# perifericos.net
KiCad netlist of a schematic drawn in Altium Designer
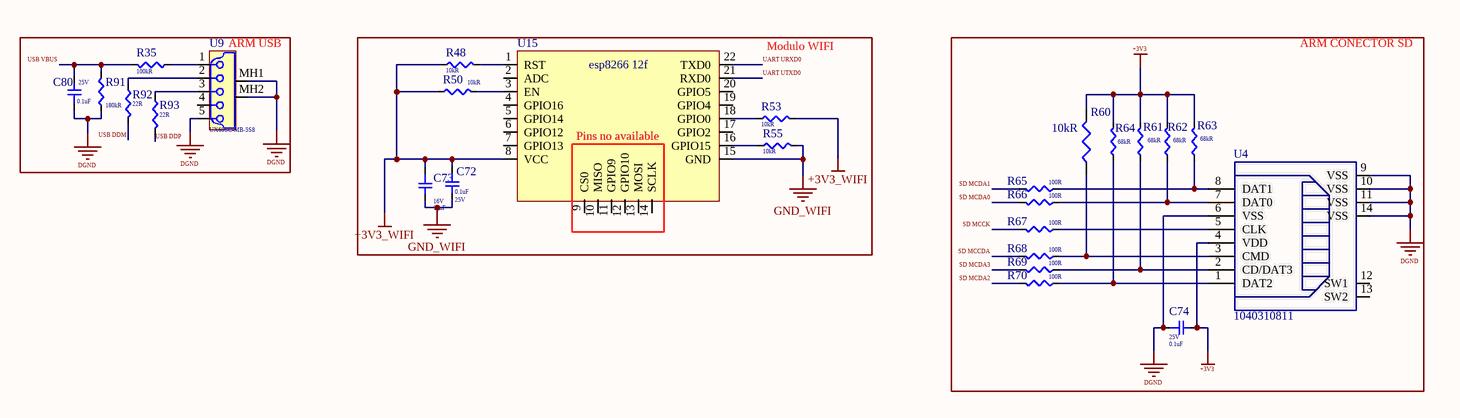
[diagram p0: perifericos.SchDoc]

(export (version "E")
  (design (tool "Eeschema 10.0.6"))
  (components
    (comp (ref "C72")
      (value "CAP_CC0805KRX7R8BB104_YAGEO")
      (footprint "CAP smd 0805 ok")
      (description "CAPACITOR, 0805, 100NF, 25V, REEL 4000")
      (fields
        (field (name "TOLERANCE") "10%")
        (field (name "VOLTAGE RATING") "25V")
        (field (name "CAPACITANCE") "0.1uF")
      )
      (libsource (lib "Cap") (part "CAP_CC0805KRX7R8BB104_YAGEO"))
    )
    (comp (ref "C73")
      (value "CAP_CL21A106KOCL3RC")
      (footprint "CAP smd 0805 OK")
      (description "CAP CER 10UF 16V X5R 0805")
      (fields
        (field (name "TOLERANCE") "10%")
        (field (name "VOLTAGE RATING") "16V")
        (field (name "CAPACITANCE") "10uF")
      )
      (libsource (lib "Cap") (part "CAP_CL21A106KOCL3RC"))
    )
    (comp (ref "C74")
      (value "CAP_CC0805KRX7R8BB104_YAGEO")
      (footprint "CAP smd 0805 ok")
      (description "CAPACITOR, 0805, 100NF, 25V, REEL 4000")
      (fields
        (field (name "TOLERANCE") "10%")
        (field (name "VOLTAGE RATING") "25V")
        (field (name "CAPACITANCE") "0.1uF")
      )
      (libsource (lib "Cap") (part "CAP_CC0805KRX7R8BB104_YAGEO"))
    )
    (comp (ref "C80")
      (value "CAP_CC0805KRX7R8BB104_YAGEO")
      (footprint "CAP smd 0805 ok")
      (description "CAPACITOR, 0805, 100NF, 25V, REEL 4000")
      (fields
        (field (name "TOLERANCE") "10%")
        (field (name "VOLTAGE RATING") "25V")
        (field (name "CAPACITANCE") "0.1uF")
      )
      (libsource (lib "Cap") (part "CAP_CC0805KRX7R8BB104_YAGEO"))
    )
    (comp (ref "R35")
      (value "AC0805JR-07100KL")
      (footprint "res 0805 ok")
      (description "Thick Film Resistors - SMD 0805  100K ohm 5% 1/8W")
      (fields (field (name "TOLERANCE") "5%") (field (name "RESISTANCE") "100kR"))
      (libsource (lib "res") (part "AC0805JR-07100KL"))
    )
    (comp (ref "R48")
      (value "RC0805JR-0710KL")
      (footprint "res 0805 ok")
      (description "Res Thick Film smd 0805 10K Ohm 5% 1/8W")
      (fields (field (name "TOLERANCE") "5%") (field (name "RESISTANCE") "10kR"))
      (libsource (lib "res") (part "RC0805JR-0710KL"))
    )
    (comp (ref "R50")
      (value "RC0805JR-0710KL")
      (footprint "res 0805 ok")
      (description "Res Thick Film smd 0805 10K Ohm 5% 1/8W")
      (fields (field (name "TOLERANCE") "5%") (field (name "RESISTANCE") "10kR"))
      (libsource (lib "res") (part "RC0805JR-0710KL"))
    )
    (comp (ref "R53")
      (value "RC0805JR-0710KL")
      (footprint "res 0805 ok")
      (description "Res Thick Film smd 0805 10K Ohm 5% 1/8W")
      (fields (field (name "TOLERANCE") "5%") (field (name "RESISTANCE") "10kR"))
      (libsource (lib "res") (part "RC0805JR-0710KL"))
    )
    (comp (ref "R55")
      (value "RC0805JR-0710KL")
      (footprint "res 0805 ok")
      (description "Res Thick Film smd 0805 10K Ohm 5% 1/8W")
      (fields (field (name "TOLERANCE") "5%") (field (name "RESISTANCE") "10kR"))
      (libsource (lib "res") (part "RC0805JR-0710KL"))
    )
    (comp (ref "R60")
      (value "RC1206JR-0768KL")
      (footprint "Res 1206 ok")
      (description "Res Thick Film smd 1206 10K Ohm 1% 0.25W(1/4W)")
      (fields (field (name "TOLERANCE") "1%") (field (name "RESISTANCE") "10kR"))
      (libsource (lib "res") (part "RC1206FR-0710KL"))
    )
    (comp (ref "R61")
      (value "RC1206JR-0768KL")
      (footprint "Res 1206 ok")
      (description "Thick Film Resistors smd 1206(3216) 68K OHM 5% 250mW")
      (fields (field (name "TOLERANCE") "5%") (field (name "RESISTANCE") "68kR"))
      (libsource (lib "res") (part "RC1206JR-0768KL"))
    )
    (comp (ref "R62")
      (value "RC1206JR-0768KL")
      (footprint "Res 1206 ok")
      (description "Thick Film Resistors smd 1206(3216) 68K OHM 5% 250mW")
      (fields (field (name "TOLERANCE") "5%") (field (name "RESISTANCE") "68kR"))
      (libsource (lib "res") (part "RC1206JR-0768KL"))
    )
    (comp (ref "R63")
      (value "RC1206JR-0768KL")
      (footprint "Res 1206 ok")
      (description "Thick Film Resistors smd 1206(3216) 68K OHM 5% 250mW")
      (fields (field (name "TOLERANCE") "5%") (field (name "RESISTANCE") "68kR"))
      (libsource (lib "res") (part "RC1206JR-0768KL"))
    )
    (comp (ref "R64")
      (value "RC1206JR-0768KL")
      (footprint "Res 1206 ok")
      (description "Thick Film Resistors smd 1206(3216) 68K OHM 5% 250mW")
      (fields (field (name "TOLERANCE") "5%") (field (name "RESISTANCE") "68kR"))
      (libsource (lib "res") (part "RC1206JR-0768KL"))
    )
    (comp (ref "R65")
      (value "RC1206JR-07100RL")
      (footprint "Res 1206 ok")
      (description "Thick Film Resistors SMD 1206 (3264)  100 OHM 5% 250mW")
      (fields (field (name "TOLERANCE") "5%") (field (name "RESISTANCE") "100R"))
      (libsource (lib "res") (part "RC1206JR-07100RL"))
    )
    (comp (ref "R66")
      (value "RC1206JR-07100RL")
      (footprint "Res 1206 ok")
      (description "Thick Film Resistors SMD 1206 (3264)  100 OHM 5% 250mW")
      (fields (field (name "TOLERANCE") "5%") (field (name "RESISTANCE") "100R"))
      (libsource (lib "res") (part "RC1206JR-07100RL"))
    )
    (comp (ref "R67")
      (value "RC1206JR-07100RL")
      (footprint "Res 1206 ok")
      (description "Thick Film Resistors SMD 1206 (3264)  100 OHM 5% 250mW")
      (fields (field (name "TOLERANCE") "5%") (field (name "RESISTANCE") "100R"))
      (libsource (lib "res") (part "RC1206JR-07100RL"))
    )
    (comp (ref "R68")
      (value "RC1206JR-07100RL")
      (footprint "Res 1206 ok")
      (description "Thick Film Resistors SMD 1206 (3264)  100 OHM 5% 250mW")
      (fields (field (name "TOLERANCE") "5%") (field (name "RESISTANCE") "100R"))
      (libsource (lib "res") (part "RC1206JR-07100RL"))
    )
    (comp (ref "R69")
      (value "RC1206JR-07100RL")
      (footprint "Res 1206 ok")
      (description "Thick Film Resistors SMD 1206 (3264)  100 OHM 5% 250mW")
      (fields (field (name "TOLERANCE") "5%") (field (name "RESISTANCE") "100R"))
      (libsource (lib "res") (part "RC1206JR-07100RL"))
    )
    (comp (ref "R70")
      (value "RC1206JR-07100RL")
      (footprint "Res 1206 ok")
      (description "Thick Film Resistors SMD 1206 (3264)  100 OHM 5% 250mW")
      (fields (field (name "TOLERANCE") "5%") (field (name "RESISTANCE") "100R"))
      (libsource (lib "res") (part "RC1206JR-07100RL"))
    )
    (comp (ref "R91")
      (value "RC1206JR-07180KL")
      (footprint "Res 1206 ok")
      (description "RES SMD 1206 180K OHM 5% 1/4W")
      (fields (field (name "TOLERANCE") "5%") (field (name "RESISTANCE") "180kR"))
      (libsource (lib "res") (part "RC1206JR-07180KL"))
    )
    (comp (ref "R92")
      (value "RC0805JR-0722RL")
      (footprint "res 0805 ok")
      (description "Res Thick Film smd  0805 22 Ohm 5% 1/8W")
      (fields (field (name "TOLERANCE") "5%") (field (name "RESISTANCE") "22R"))
      (libsource (lib "res") (part "RC0805JR-0722RL"))
    )
    (comp (ref "R93")
      (value "RC0805JR-0722RL")
      (footprint "res 0805 ok")
      (description "Res Thick Film smd  0805 22 Ohm 5% 1/8W")
      (fields (field (name "TOLERANCE") "5%") (field (name "RESISTANCE") "22R"))
      (libsource (lib "res") (part "RC0805JR-0722RL"))
    )
    (comp (ref "U4")
      (value "1040310811")
      (footprint "micro sd")
      (libsource (lib "others") (part "1040310811"))
    )
    (comp (ref "U9")
      (value "UX60SC-MB-5S8")
      (description "Conn Mini USB 2.0 Type B RCP 5 POS 0.8mm Solder RA SMD 5 Terminal 1 Port Embossed T/R")
      (libsource (lib "conectors") (part "UX60SC-MB-5S8"))
    )
    (comp (ref "U15")
      (value "esp8266 12f")
      (footprint "modulo wifi ok")
      (libsource (lib "ic") (part "esp8266 12f"))
    )
  )
  (nets
    (net (code "1") (name "+3V3") (class "Default")
      (node (ref "C74") (pin "22") (pinfunction "22_22") (pintype "passive"))
      (node (ref "R60") (pin "1") (pinfunction "1_1") (pintype "passive"))
      (node (ref "R61") (pin "1") (pintype "passive"))
      (node (ref "R62") (pin "1") (pintype "passive"))
      (node (ref "R63") (pin "1") (pintype "passive"))
      (node (ref "R64") (pin "1") (pintype "passive"))
      (node (ref "U4") (pin "4") (pinfunction "VDD_4") (pintype "passive"))
    )
    (net (code "2") (name "+3V3_WIFI") (class "Default")
      (node (ref "C72") (pin "23") (pinfunction "23_23") (pintype "passive"))
      (node (ref "C73") (pin "23") (pinfunction "23_23") (pintype "passive"))
      (node (ref "R48") (pin "2") (pinfunction "2_2") (pintype "passive"))
      (node (ref "R50") (pin "2") (pinfunction "2_2") (pintype "passive"))
      (node (ref "R53") (pin "1") (pintype "passive"))
      (node (ref "U15") (pin "8") (pinfunction "VCC_8") (pintype "passive"))
    )
    (net (code "3") (name "/SD MCCDA") (class "Default") (node (ref "R68") (pin "1") (pintype "passive")))
    (net (code "4") (name "/SD MCCK") (class "Default") (node (ref "R67") (pin "1") (pintype "passive")))
    (net (code "5") (name "/SD MCDA0") (class "Default") (node (ref "R66") (pin "1") (pintype "passive")))
    (net (code "6") (name "/SD MCDA1") (class "Default") (node (ref "R65") (pin "1") (pintype "passive")))
    (net (code "7") (name "/SD MCDA2") (class "Default") (node (ref "R70") (pin "1") (pintype "passive")))
    (net (code "8") (name "/SD MCDA3") (class "Default") (node (ref "R69") (pin "1") (pintype "passive")))
    (net (code "9") (name "/UART URXD0") (class "Default")
      (node (ref "U15") (pin "22") (pinfunction "TXD0_22") (pintype "passive"))
    )
    (net (code "10") (name "/UART UTXD0") (class "Default")
      (node (ref "U15") (pin "21") (pinfunction "RXD0_21") (pintype "passive"))
    )
    (net (code "11") (name "/USB DDM") (class "Default") (node (ref "R92") (pin "1") (pintype "passive")))
    (net (code "12") (name "/USB DDP") (class "Default") (node (ref "R93") (pin "1") (pintype "passive")))
    (net (code "13") (name "/USB VBUS") (class "Default")
      (node (ref "C80") (pin "22") (pinfunction "22_22") (pintype "passive"))
      (node (ref "R35") (pin "2") (pinfunction "2_2") (pintype "passive"))
      (node (ref "R91") (pin "1") (pinfunction "1_1") (pintype "passive"))
    )
    (net (code "14") (name "DGND") (class "Default")
      (node (ref "C74") (pin "23") (pinfunction "23_23") (pintype "passive"))
      (node (ref "C80") (pin "23") (pinfunction "23_23") (pintype "passive"))
      (node (ref "R91") (pin "2") (pinfunction "2_2") (pintype "passive"))
      (node (ref "U4") (pin "10") (pinfunction "VSS_10") (pintype "passive"))
      (node (ref "U4") (pin "11") (pinfunction "VSS_11") (pintype "passive"))
      (node (ref "U4") (pin "14") (pinfunction "VSS_14") (pintype "passive"))
      (node (ref "U4") (pin "6") (pinfunction "VSS_6") (pintype "passive"))
      (node (ref "U4") (pin "9") (pinfunction "VSS_9") (pintype "passive"))
      (node (ref "U9") (pin "5") (pinfunction "5_5") (pintype "passive"))
      (node (ref "U9") (pin "MH1") (pinfunction "6_MH1") (pintype "passive"))
      (node (ref "U9") (pin "MH2") (pinfunction "7_MH2") (pintype "passive"))
    )
    (net (code "15") (name "GND_WIFI") (class "Default")
      (node (ref "C72") (pin "22") (pinfunction "22_22") (pintype "passive"))
      (node (ref "C73") (pin "22") (pinfunction "22_22") (pintype "passive"))
      (node (ref "R55") (pin "1") (pintype "passive"))
      (node (ref "U15") (pin "15") (pinfunction "GND_15") (pintype "passive"))
    )
    (net (code "16") (name "Net-(R35-Pad1)") (class "Default")
      (node (ref "R35") (pin "1") (pinfunction "1_1") (pintype "passive"))
      (node (ref "U9") (pin "1") (pinfunction "1_1") (pintype "passive"))
    )
    (net (code "17") (name "Net-(R92-Pad2)") (class "Default")
      (node (ref "R92") (pin "2") (pinfunction "2_2") (pintype "passive"))
      (node (ref "U9") (pin "2") (pinfunction "2_2") (pintype "passive"))
    )
    (net (code "18") (name "Net-(R93-Pad2)") (class "Default")
      (node (ref "R93") (pin "2") (pinfunction "2_2") (pintype "passive"))
      (node (ref "U9") (pin "3") (pinfunction "3_3") (pintype "passive"))
    )
    (net (code "19") (name "Net-(U4-CD{slash}DAT3)") (class "Default")
      (node (ref "R61") (pin "2") (pinfunction "2_2") (pintype "passive"))
      (node (ref "R69") (pin "2") (pinfunction "2_2") (pintype "passive"))
      (node (ref "U4") (pin "2") (pinfunction "CD/DAT3_2") (pintype "passive"))
    )
    (net (code "20") (name "Net-(U4-CLK)") (class "Default")
      (node (ref "R67") (pin "2") (pinfunction "2_2") (pintype "passive"))
      (node (ref "U4") (pin "5") (pinfunction "CLK_5") (pintype "passive"))
    )
    (net (code "21") (name "Net-(U4-CMD)") (class "Default")
      (node (ref "R60") (pin "2") (pinfunction "2_2") (pintype "passive"))
      (node (ref "R68") (pin "2") (pinfunction "2_2") (pintype "passive"))
      (node (ref "U4") (pin "3") (pinfunction "CMD_3") (pintype "passive"))
    )
    (net (code "22") (name "Net-(U4-DAT0)") (class "Default")
      (node (ref "R62") (pin "2") (pinfunction "2_2") (pintype "passive"))
      (node (ref "R66") (pin "2") (pinfunction "2_2") (pintype "passive"))
      (node (ref "U4") (pin "7") (pinfunction "DAT0_7") (pintype "passive"))
    )
    (net (code "23") (name "Net-(U4-DAT1)") (class "Default")
      (node (ref "R63") (pin "2") (pinfunction "2_2") (pintype "passive"))
      (node (ref "R65") (pin "2") (pinfunction "2_2") (pintype "passive"))
      (node (ref "U4") (pin "8") (pinfunction "DAT1_8") (pintype "passive"))
    )
    (net (code "24") (name "Net-(U4-DAT2)") (class "Default")
      (node (ref "R64") (pin "2") (pinfunction "2_2") (pintype "passive"))
      (node (ref "R70") (pin "2") (pinfunction "2_2") (pintype "passive"))
      (node (ref "U4") (pin "1") (pinfunction "DAT2_1") (pintype "passive"))
    )
    (net (code "25") (name "Net-(U15-EN)") (class "Default")
      (node (ref "R50") (pin "1") (pintype "passive"))
      (node (ref "U15") (pin "3") (pinfunction "EN_3") (pintype "passive"))
    )
    (net (code "26") (name "Net-(U15-GPIO0)") (class "Default")
      (node (ref "R53") (pin "2") (pinfunction "2_2") (pintype "passive"))
      (node (ref "U15") (pin "18") (pinfunction "GPIO0_18") (pintype "passive"))
    )
    (net (code "27") (name "Net-(U15-GPIO15)") (class "Default")
      (node (ref "R55") (pin "2") (pinfunction "2_2") (pintype "passive"))
      (node (ref "U15") (pin "16") (pinfunction "GPIO15_16") (pintype "passive"))
    )
    (net (code "28") (name "Net-(U15-RST)") (class "Default")
      (node (ref "R48") (pin "1") (pintype "passive"))
      (node (ref "U15") (pin "1") (pinfunction "RST_1") (pintype "passive"))
    )
    (net (code "29") (name "unconnected-(U4-SW1-Pad12)") (class "Default")
      (node (ref "U4") (pin "12") (pinfunction "SW1_12") (pintype "passive"))
    )
    (net (code "30") (name "unconnected-(U4-SW2-Pad13)") (class "Default")
      (node (ref "U4") (pin "13") (pinfunction "SW2_13") (pintype "passive"))
    )
    (net (code "31") (name "unconnected-(U9-Pad4)") (class "Default")
      (node (ref "U9") (pin "4") (pinfunction "4_4") (pintype "passive"))
    )
    (net (code "32") (name "unconnected-(U15-ADC-Pad2)") (class "Default")
      (node (ref "U15") (pin "2") (pinfunction "ADC_2") (pintype "passive"))
    )
    (net (code "33") (name "unconnected-(U15-CS0-Pad9)") (class "Default")
      (node (ref "U15") (pin "9") (pinfunction "CS0_9") (pintype "passive"))
    )
    (net (code "34") (name "unconnected-(U15-GPIO2-Pad17)") (class "Default")
      (node (ref "U15") (pin "17") (pinfunction "GPIO2_17") (pintype "passive"))
    )
    (net (code "35") (name "unconnected-(U15-GPIO4-Pad19)") (class "Default")
      (node (ref "U15") (pin "19") (pinfunction "GPIO4_19") (pintype "passive"))
    )
    (net (code "36") (name "unconnected-(U15-GPIO5-Pad20)") (class "Default")
      (node (ref "U15") (pin "20") (pinfunction "GPIO5_20") (pintype "passive"))
    )
    (net (code "37") (name "unconnected-(U15-GPIO9-Pad11)") (class "Default")
      (node (ref "U15") (pin "11") (pinfunction "GPIO9_11") (pintype "passive"))
    )
    (net (code "38") (name "unconnected-(U15-GPIO10-Pad12)") (class "Default")
      (node (ref "U15") (pin "12") (pinfunction "GPIO10_12") (pintype "passive"))
    )
    (net (code "39") (name "unconnected-(U15-GPIO12-Pad6)") (class "Default")
      (node (ref "U15") (pin "6") (pinfunction "GPIO12_6") (pintype "passive"))
    )
    (net (code "40") (name "unconnected-(U15-GPIO13-Pad7)") (class "Default")
      (node (ref "U15") (pin "7") (pinfunction "GPIO13_7") (pintype "passive"))
    )
    (net (code "41") (name "unconnected-(U15-GPIO14-Pad5)") (class "Default")
      (node (ref "U15") (pin "5") (pinfunction "GPIO14_5") (pintype "passive"))
    )
    (net (code "42") (name "unconnected-(U15-GPIO16-Pad4)") (class "Default")
      (node (ref "U15") (pin "4") (pinfunction "GPIO16_4") (pintype "passive"))
    )
    (net (code "43") (name "unconnected-(U15-MISO-Pad10)") (class "Default")
      (node (ref "U15") (pin "10") (pinfunction "MISO_10") (pintype "passive"))
    )
    (net (code "44") (name "unconnected-(U15-MOSI-Pad13)") (class "Default")
      (node (ref "U15") (pin "13") (pinfunction "MOSI_13") (pintype "passive"))
    )
    (net (code "45") (name "unconnected-(U15-SCLK-Pad14)") (class "Default")
      (node (ref "U15") (pin "14") (pinfunction "SCLK_14") (pintype "passive"))
    )
  )
)
